# Seguidordelinea.net
KiCad netlist of a schematic drawn in Altium Designer
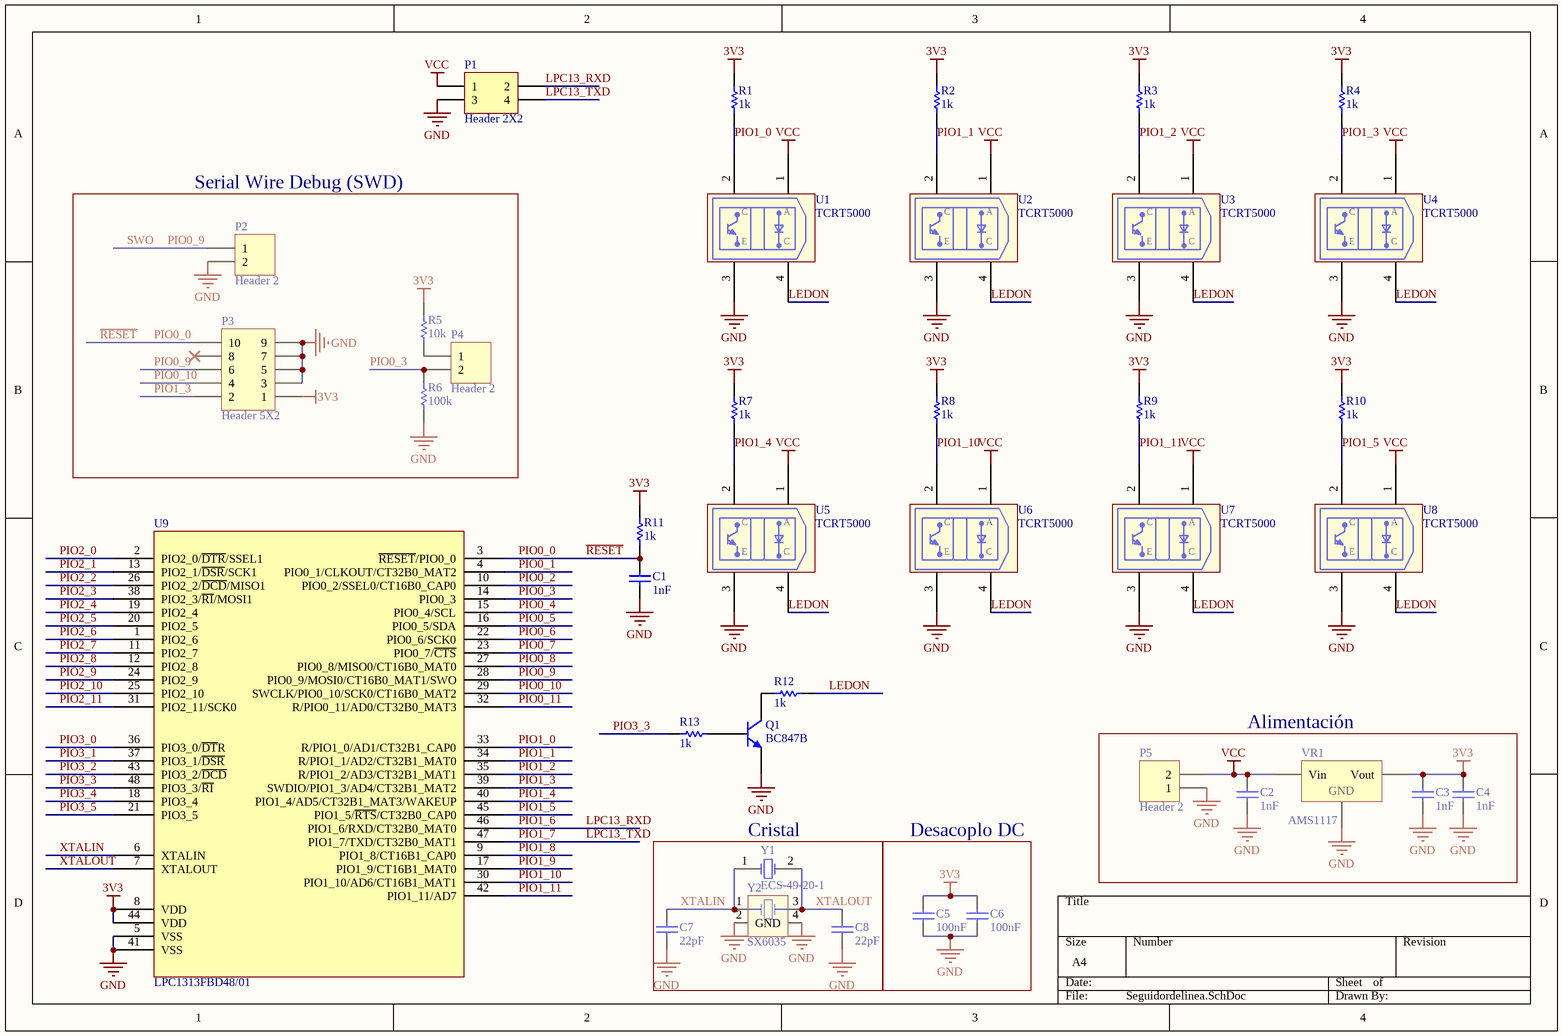
[diagram p0: Seguidordelinea.SchDoc]

(export (version "E")
  (design (tool "Eeschema 10.0.6"))
  (components
    (comp (ref "C1")
      (value "1nF")
      (footprint "0805_CAP")
      (fields (field (name "Comment") "Capacitor"))
      (libsource (lib "epf") (part "Cap"))
    )
    (comp (ref "C2")
      (value "1nF")
      (footprint "0805_CAP")
      (fields (field (name "Comment") "Capacitor"))
      (libsource (lib "epf") (part "Cap"))
    )
    (comp (ref "C3")
      (value "1nF")
      (footprint "0805_CAP")
      (fields (field (name "Comment") "Capacitor"))
      (libsource (lib "epf") (part "Cap"))
    )
    (comp (ref "C4")
      (value "1nF")
      (footprint "0805_CAP")
      (fields (field (name "Comment") "Capacitor"))
      (libsource (lib "epf") (part "Cap"))
    )
    (comp (ref "C5")
      (value "100nF")
      (footprint "0805_CAP")
      (fields (field (name "Comment") "Capacitor"))
      (libsource (lib "epf") (part "Cap"))
    )
    (comp (ref "C6")
      (value "100nF")
      (footprint "0805_CAP")
      (fields (field (name "Comment") "Capacitor"))
      (libsource (lib "epf") (part "Cap"))
    )
    (comp (ref "C7")
      (value "22pF")
      (footprint "0805_CAP")
      (fields (field (name "Comment") "Capacitor"))
      (libsource (lib "epf") (part "Cap"))
    )
    (comp (ref "C8")
      (value "22pF")
      (footprint "0805_CAP")
      (fields (field (name "Comment") "Capacitor"))
      (libsource (lib "epf") (part "Cap"))
    )
    (comp (ref "P1")
      (value "Header 2X2")
      (footprint "HDR2X2")
      (description "Header, 2-Pin, Dual row")
      (fields (field (name "PUBLISHER") "Altium Limited"))
      (libsource (lib "Miscellaneous Connectors") (part "Header 2X2"))
    )
    (comp (ref "P2")
      (value "Header 2")
      (footprint "HDR1X2")
      (description "Header, 2-Pin")
      (fields (field (name "PUBLISHER") "Altium Limited"))
      (libsource (lib "Miscellaneous Connectors") (part "Header 2"))
    )
    (comp (ref "P3")
      (value "Header 5X2")
      (footprint "HDR2X5")
      (description "Header, 5-Pin, Dual row")
      (fields (field (name "PUBLISHER") "Altium Limited"))
      (libsource (lib "epf") (part "Header 5X2"))
    )
    (comp (ref "P4")
      (value "Header 2")
      (footprint "HDR1X2")
      (description "Header, 2-Pin")
      (fields (field (name "PUBLISHER") "Altium Limited"))
      (libsource (lib "Miscellaneous Connectors") (part "Header 2"))
    )
    (comp (ref "P5")
      (value "Header 2")
      (footprint "HDR1X2")
      (description "Header, 2-Pin")
      (fields (field (name "PUBLISHER") "Altium Limited"))
      (libsource (lib "") (part "Header 2_1"))
    )
    (comp (ref "Q1")
      (value "BC847B")
      (footprint "SOT23")
      (description "NPN 100MHz")
      (libsource (lib "epf") (part "BC847B"))
    )
    (comp (ref "R1")
      (value "1k")
      (footprint "0805_RES")
      (fields (field (name "Comment") "Resistor"))
      (libsource (lib "epf") (part "Res"))
    )
    (comp (ref "R2")
      (value "1k")
      (footprint "0805_RES")
      (fields (field (name "Comment") "Resistor"))
      (libsource (lib "epf") (part "Res"))
    )
    (comp (ref "R3")
      (value "1k")
      (footprint "0805_RES")
      (fields (field (name "Comment") "Resistor"))
      (libsource (lib "epf") (part "Res"))
    )
    (comp (ref "R4")
      (value "1k")
      (footprint "0805_RES")
      (fields (field (name "Comment") "Resistor"))
      (libsource (lib "epf") (part "Res"))
    )
    (comp (ref "R5")
      (value "10k")
      (footprint "0805_RES")
      (fields (field (name "Comment") "Resistor"))
      (libsource (lib "epf") (part "Res"))
    )
    (comp (ref "R6")
      (value "100k")
      (footprint "0805_RES")
      (fields (field (name "Comment") "Resistor"))
      (libsource (lib "epf") (part "Res"))
    )
    (comp (ref "R7")
      (value "1k")
      (footprint "0805_RES")
      (fields (field (name "Comment") "Resistor"))
      (libsource (lib "epf") (part "Res"))
    )
    (comp (ref "R8")
      (value "1k")
      (footprint "0805_RES")
      (fields (field (name "Comment") "Resistor"))
      (libsource (lib "epf") (part "Res"))
    )
    (comp (ref "R9")
      (value "1k")
      (footprint "0805_RES")
      (fields (field (name "Comment") "Resistor"))
      (libsource (lib "epf") (part "Res"))
    )
    (comp (ref "R10")
      (value "1k")
      (footprint "0805_RES")
      (fields (field (name "Comment") "Resistor"))
      (libsource (lib "epf") (part "Res"))
    )
    (comp (ref "R11")
      (value "1k")
      (footprint "0805_RES")
      (fields (field (name "Comment") "Resistor"))
      (libsource (lib "epf") (part "Res"))
    )
    (comp (ref "R12")
      (value "1k")
      (footprint "0805_RES")
      (fields (field (name "Comment") "Resistor"))
      (libsource (lib "epf") (part "Res"))
    )
    (comp (ref "R13")
      (value "1k")
      (footprint "0805_RES")
      (fields (field (name "Comment") "Resistor"))
      (libsource (lib "epf") (part "Res"))
    )
    (comp (ref "U1") (value "TCRT5000") (footprint "TCRT5000") (libsource (lib "epf") (part "TCRT5000")))
    (comp (ref "U2") (value "TCRT5000") (footprint "TCRT5000") (libsource (lib "epf") (part "TCRT5000")))
    (comp (ref "U3") (value "TCRT5000") (footprint "TCRT5000") (libsource (lib "epf") (part "TCRT5000")))
    (comp (ref "U4") (value "TCRT5000") (footprint "TCRT5000") (libsource (lib "epf") (part "TCRT5000")))
    (comp (ref "U5") (value "TCRT5000") (footprint "TCRT5000") (libsource (lib "epf") (part "TCRT5000")))
    (comp (ref "U6") (value "TCRT5000") (footprint "TCRT5000") (libsource (lib "epf") (part "TCRT5000")))
    (comp (ref "U7") (value "TCRT5000") (footprint "TCRT5000") (libsource (lib "epf") (part "TCRT5000")))
    (comp (ref "U8") (value "TCRT5000") (footprint "TCRT5000") (libsource (lib "epf") (part "TCRT5000")))
    (comp (ref "U9")
      (value "LPC1313FBD48/01")
      (footprint "TQFP48_LPC1343")
      (description "ARM CortexM3 32K Flash, 8k RAM")
      (libsource (lib "epf") (part "LPC1313FBD48/01"))
    )
    (comp (ref "VR1")
      (value "AMS1117")
      (footprint "SOT-223 - M3")
      (description "Voltage Regulator")
      (fields (field (name "PUBLISHER") "Altium Limited"))
      (libsource (lib "epf") (part "AMS1117"))
    )
    (comp (ref "Y1")
      (value "ECS-49-20-1")
      (footprint "HC-49U")
      (description "Crystal Oscillator")
      (fields (field (name "PUBLISHER") "Altium Limited"))
      (libsource (lib "ECS Crystal Oscillator") (part "ECS-49-20-1"))
    )
    (comp (ref "Y2") (value "SX6035") (footprint "SX6035") (libsource (lib "epf") (part "XTAL_SX6035")))
  )
  (nets
    (net (code "1") (name "/LEDON") (class "Default")
      (node (ref "R12") (pin "2") (pinfunction "2_2") (pintype "passive"))
      (node (ref "U1") (pin "4") (pinfunction "C_4") (pintype "passive"))
      (node (ref "U2") (pin "4") (pinfunction "C_4") (pintype "passive"))
      (node (ref "U3") (pin "4") (pinfunction "C_4") (pintype "passive"))
      (node (ref "U4") (pin "4") (pinfunction "C_4") (pintype "passive"))
      (node (ref "U5") (pin "4") (pinfunction "C_4") (pintype "passive"))
      (node (ref "U6") (pin "4") (pinfunction "C_4") (pintype "passive"))
      (node (ref "U7") (pin "4") (pinfunction "C_4") (pintype "passive"))
      (node (ref "U8") (pin "4") (pinfunction "C_4") (pintype "passive"))
    )
    (net (code "2") (name "/LPC13_RXD") (class "Default")
      (node (ref "P1") (pin "2") (pinfunction "2_2") (pintype "passive"))
      (node (ref "U9") (pin "46") (pinfunction "PIO1_6/RXD/CT32B0_MAT0_46") (pintype "passive"))
    )
    (net (code "3") (name "/LPC13_TXD") (class "Default")
      (node (ref "P1") (pin "4") (pinfunction "4_4") (pintype "passive"))
      (node (ref "U9") (pin "47") (pinfunction "PIO1_7/TXD/CT32B0_MAT1_47") (pintype "passive"))
    )
    (net (code "4") (name "/PIO0_0") (class "Default")
      (node (ref "C1") (pin "2") (pinfunction "2_2") (pintype "passive"))
      (node (ref "P3") (pin "10") (pinfunction "10_10") (pintype "passive"))
      (node (ref "R11") (pin "1") (pinfunction "1_1") (pintype "passive"))
      (node (ref "U9") (pin "3") (pinfunction "~{RESET}/PIO0_0_3") (pintype "passive"))
    )
    (net (code "5") (name "/PIO0_1") (class "Default")
      (node (ref "U9") (pin "4") (pinfunction "PIO0_1/CLKOUT/CT32B0_MAT2_4") (pintype "passive"))
    )
    (net (code "6") (name "/PIO0_2") (class "Default")
      (node (ref "U9") (pin "10") (pinfunction "PIO0_2/SSEL0/CT16B0_CAP0_10") (pintype "passive"))
    )
    (net (code "7") (name "/PIO0_3") (class "Default")
      (node (ref "P4") (pin "2") (pinfunction "2_2") (pintype "passive"))
      (node (ref "R6") (pin "1") (pinfunction "1_1") (pintype "passive"))
      (node (ref "U9") (pin "14") (pinfunction "PIO0_3_14") (pintype "passive"))
    )
    (net (code "8") (name "/PIO0_4") (class "Default")
      (node (ref "U9") (pin "15") (pinfunction "PIO0_4/SCL_15") (pintype "passive"))
    )
    (net (code "9") (name "/PIO0_5") (class "Default")
      (node (ref "U9") (pin "16") (pinfunction "PIO0_5/SDA_16") (pintype "passive"))
    )
    (net (code "10") (name "/PIO0_6") (class "Default")
      (node (ref "U9") (pin "22") (pinfunction "PIO0_6/SCK0_22") (pintype "passive"))
    )
    (net (code "11") (name "/PIO0_7") (class "Default")
      (node (ref "U9") (pin "23") (pinfunction "PIO0_7/~{CTS}_23") (pintype "passive"))
    )
    (net (code "12") (name "/PIO0_8") (class "Default")
      (node (ref "U9") (pin "27") (pinfunction "PIO0_8/MISO0/CT16B0_MAT0_27") (pintype "passive"))
    )
    (net (code "13") (name "/PIO0_9") (class "Default")
      (node (ref "P2") (pin "1") (pinfunction "1_1") (pintype "passive"))
      (node (ref "P3") (pin "6") (pinfunction "6_6") (pintype "passive"))
      (node (ref "U9") (pin "28") (pinfunction "PIO0_9/MOSI0/CT16B0_MAT1/SWO_28") (pintype "passive"))
    )
    (net (code "14") (name "/PIO0_10") (class "Default")
      (node (ref "P3") (pin "4") (pinfunction "4_4") (pintype "passive"))
      (node (ref "U9") (pin "29") (pinfunction "SWCLK/PIO0_10/SCK0/CT16B0_MAT2_29") (pintype "passive"))
    )
    (net (code "15") (name "/PIO0_11") (class "Default")
      (node (ref "U9") (pin "32") (pinfunction "R/PIO0_11/AD0/CT32B0_MAT3_32") (pintype "passive"))
    )
    (net (code "16") (name "/PIO1_0") (class "Default")
      (node (ref "R1") (pin "2") (pinfunction "2_2") (pintype "passive"))
      (node (ref "U1") (pin "2") (pinfunction "C_2") (pintype "passive"))
      (node (ref "U9") (pin "33") (pinfunction "R/PIO1_0/AD1/CT32B1_CAP0_33") (pintype "passive"))
    )
    (net (code "17") (name "/PIO1_1") (class "Default")
      (node (ref "R2") (pin "2") (pinfunction "2_2") (pintype "passive"))
      (node (ref "U2") (pin "2") (pinfunction "C_2") (pintype "passive"))
      (node (ref "U9") (pin "34") (pinfunction "R/PIO1_1/AD2/CT32B1_MAT0_34") (pintype "passive"))
    )
    (net (code "18") (name "/PIO1_2") (class "Default")
      (node (ref "R3") (pin "2") (pinfunction "2_2") (pintype "passive"))
      (node (ref "U3") (pin "2") (pinfunction "C_2") (pintype "passive"))
      (node (ref "U9") (pin "35") (pinfunction "R/PIO1_2/AD3/CT32B1_MAT1_35") (pintype "passive"))
    )
    (net (code "19") (name "/PIO1_3") (class "Default")
      (node (ref "P3") (pin "2") (pinfunction "2_2") (pintype "passive"))
      (node (ref "R4") (pin "2") (pinfunction "2_2") (pintype "passive"))
      (node (ref "U4") (pin "2") (pinfunction "C_2") (pintype "passive"))
      (node (ref "U9") (pin "39") (pinfunction "SWDIO/PIO1_3/AD4/CT32B1_MAT2_39") (pintype "passive"))
    )
    (net (code "20") (name "/PIO1_4") (class "Default")
      (node (ref "R7") (pin "2") (pinfunction "2_2") (pintype "passive"))
      (node (ref "U5") (pin "2") (pinfunction "C_2") (pintype "passive"))
      (node (ref "U9") (pin "40") (pinfunction "PIO1_4/AD5/CT32B1_MAT3/WAKEUP_40") (pintype "passive"))
    )
    (net (code "21") (name "/PIO1_5") (class "Default")
      (node (ref "R10") (pin "2") (pinfunction "2_2") (pintype "passive"))
      (node (ref "U8") (pin "2") (pinfunction "C_2") (pintype "passive"))
      (node (ref "U9") (pin "45") (pinfunction "PIO1_5/~{RTS}/CT32B0_CAP0_45") (pintype "passive"))
    )
    (net (code "22") (name "/PIO1_8") (class "Default")
      (node (ref "U9") (pin "9") (pinfunction "PIO1_8/CT16B1_CAP0_9") (pintype "passive"))
    )
    (net (code "23") (name "/PIO1_9") (class "Default")
      (node (ref "U9") (pin "17") (pinfunction "PIO1_9/CT16B1_MAT0_17") (pintype "passive"))
    )
    (net (code "24") (name "/PIO1_10") (class "Default")
      (node (ref "R8") (pin "2") (pinfunction "2_2") (pintype "passive"))
      (node (ref "U6") (pin "2") (pinfunction "C_2") (pintype "passive"))
      (node (ref "U9") (pin "30") (pinfunction "PIO1_10/AD6/CT16B1_MAT1_30") (pintype "passive"))
    )
    (net (code "25") (name "/PIO1_11") (class "Default")
      (node (ref "R9") (pin "2") (pinfunction "2_2") (pintype "passive"))
      (node (ref "U7") (pin "2") (pinfunction "C_2") (pintype "passive"))
      (node (ref "U9") (pin "42") (pinfunction "PIO1_11/AD7_42") (pintype "passive"))
    )
    (net (code "26") (name "/PIO2_0") (class "Default")
      (node (ref "U9") (pin "2") (pinfunction "PIO2_0/~{DTR}/SSEL1_2") (pintype "passive"))
    )
    (net (code "27") (name "/PIO2_1") (class "Default")
      (node (ref "U9") (pin "13") (pinfunction "PIO2_1/~{DSR}/SCK1_13") (pintype "passive"))
    )
    (net (code "28") (name "/PIO2_2") (class "Default")
      (node (ref "U9") (pin "26") (pinfunction "PIO2_2/~{DCD}/MISO1_26") (pintype "passive"))
    )
    (net (code "29") (name "/PIO2_3") (class "Default")
      (node (ref "U9") (pin "38") (pinfunction "PIO2_3/~{RI}/MOSI1_38") (pintype "passive"))
    )
    (net (code "30") (name "/PIO2_4") (class "Default")
      (node (ref "U9") (pin "19") (pinfunction "PIO2_4_19") (pintype "passive"))
    )
    (net (code "31") (name "/PIO2_5") (class "Default")
      (node (ref "U9") (pin "20") (pinfunction "PIO2_5_20") (pintype "passive"))
    )
    (net (code "32") (name "/PIO2_6") (class "Default")
      (node (ref "U9") (pin "1") (pinfunction "PIO2_6_1") (pintype "passive"))
    )
    (net (code "33") (name "/PIO2_7") (class "Default")
      (node (ref "U9") (pin "11") (pinfunction "PIO2_7_11") (pintype "passive"))
    )
    (net (code "34") (name "/PIO2_8") (class "Default")
      (node (ref "U9") (pin "12") (pinfunction "PIO2_8_12") (pintype "passive"))
    )
    (net (code "35") (name "/PIO2_9") (class "Default")
      (node (ref "U9") (pin "24") (pinfunction "PIO2_9_24") (pintype "passive"))
    )
    (net (code "36") (name "/PIO2_10") (class "Default")
      (node (ref "U9") (pin "25") (pinfunction "PIO2_10_25") (pintype "passive"))
    )
    (net (code "37") (name "/PIO2_11") (class "Default")
      (node (ref "U9") (pin "31") (pinfunction "PIO2_11/SCK0_31") (pintype "passive"))
    )
    (net (code "38") (name "/PIO3_0") (class "Default")
      (node (ref "U9") (pin "36") (pinfunction "PIO3_0/~{DT}R_36") (pintype "passive"))
    )
    (net (code "39") (name "/PIO3_1") (class "Default")
      (node (ref "U9") (pin "37") (pinfunction "PIO3_1/~{DSR}_37") (pintype "passive"))
    )
    (net (code "40") (name "/PIO3_2") (class "Default")
      (node (ref "U9") (pin "43") (pinfunction "PIO3_2/~{DCD}_43") (pintype "passive"))
    )
    (net (code "41") (name "/PIO3_3") (class "Default")
      (node (ref "R13") (pin "1") (pinfunction "1_1") (pintype "passive"))
      (node (ref "U9") (pin "48") (pinfunction "PIO3_3/~{RI}_48") (pintype "passive"))
    )
    (net (code "42") (name "/PIO3_4") (class "Default")
      (node (ref "U9") (pin "18") (pinfunction "PIO3_4_18") (pintype "passive"))
    )
    (net (code "43") (name "/PIO3_5") (class "Default")
      (node (ref "U9") (pin "21") (pinfunction "PIO3_5_21") (pintype "passive"))
    )
    (net (code "44") (name "/XTALIN") (class "Default")
      (node (ref "C7") (pin "2") (pinfunction "2_2") (pintype "passive"))
      (node (ref "U9") (pin "6") (pinfunction "XTALIN_6") (pintype "passive"))
      (node (ref "Y1") (pin "1") (pinfunction "OSC1_1") (pintype "passive"))
      (node (ref "Y2") (pin "1") (pinfunction "XTAL_1") (pintype "passive"))
    )
    (net (code "45") (name "/XTALOUT") (class "Default")
      (node (ref "C8") (pin "1") (pinfunction "1_1") (pintype "passive"))
      (node (ref "U9") (pin "7") (pinfunction "XTALOUT_7") (pintype "passive"))
      (node (ref "Y1") (pin "2") (pinfunction "OSC2_2") (pintype "passive"))
      (node (ref "Y2") (pin "3") (pinfunction "XTAL_3") (pintype "passive"))
    )
    (net (code "46") (name "3V3") (class "Default")
      (node (ref "C3") (pin "2") (pinfunction "2_2") (pintype "passive"))
      (node (ref "C4") (pin "2") (pinfunction "2_2") (pintype "passive"))
      (node (ref "C5") (pin "2") (pinfunction "2_2") (pintype "passive"))
      (node (ref "C6") (pin "2") (pinfunction "2_2") (pintype "passive"))
      (node (ref "P3") (pin "1") (pinfunction "1_1") (pintype "passive"))
      (node (ref "R1") (pin "1") (pinfunction "1_1") (pintype "passive"))
      (node (ref "R10") (pin "1") (pinfunction "1_1") (pintype "passive"))
      (node (ref "R11") (pin "2") (pinfunction "2_2") (pintype "passive"))
      (node (ref "R2") (pin "1") (pinfunction "1_1") (pintype "passive"))
      (node (ref "R3") (pin "1") (pinfunction "1_1") (pintype "passive"))
      (node (ref "R4") (pin "1") (pinfunction "1_1") (pintype "passive"))
      (node (ref "R5") (pin "1") (pinfunction "1_1") (pintype "passive"))
      (node (ref "R7") (pin "1") (pinfunction "1_1") (pintype "passive"))
      (node (ref "R8") (pin "1") (pinfunction "1_1") (pintype "passive"))
      (node (ref "R9") (pin "1") (pinfunction "1_1") (pintype "passive"))
      (node (ref "U9") (pin "44") (pinfunction "VDD_44") (pintype "passive"))
      (node (ref "U9") (pin "8") (pinfunction "VDD_8") (pintype "passive"))
      (node (ref "VR1") (pin "2") (pinfunction "Vout_2") (pintype "passive"))
    )
    (net (code "47") (name "GND") (class "Default")
      (node (ref "C1") (pin "1") (pinfunction "1_1") (pintype "passive"))
      (node (ref "C2") (pin "1") (pinfunction "1_1") (pintype "passive"))
      (node (ref "C3") (pin "1") (pinfunction "1_1") (pintype "passive"))
      (node (ref "C4") (pin "1") (pinfunction "1_1") (pintype "passive"))
      (node (ref "C5") (pin "1") (pinfunction "1_1") (pintype "passive"))
      (node (ref "C6") (pin "1") (pinfunction "1_1") (pintype "passive"))
      (node (ref "C7") (pin "1") (pinfunction "1_1") (pintype "passive"))
      (node (ref "C8") (pin "2") (pinfunction "2_2") (pintype "passive"))
      (node (ref "P1") (pin "3") (pinfunction "3_3") (pintype "passive"))
      (node (ref "P2") (pin "2") (pinfunction "2_2") (pintype "passive"))
      (node (ref "P3") (pin "3") (pinfunction "3_3") (pintype "passive"))
      (node (ref "P3") (pin "5") (pinfunction "5_5") (pintype "passive"))
      (node (ref "P3") (pin "7") (pinfunction "7_7") (pintype "passive"))
      (node (ref "P3") (pin "9") (pinfunction "9_9") (pintype "passive"))
      (node (ref "P5") (pin "1") (pinfunction "1_1") (pintype "passive"))
      (node (ref "Q1") (pin "2") (pinfunction "E_2") (pintype "passive"))
      (node (ref "R6") (pin "2") (pinfunction "2_2") (pintype "passive"))
      (node (ref "U1") (pin "3") (pinfunction "E_3") (pintype "passive"))
      (node (ref "U2") (pin "3") (pinfunction "E_3") (pintype "passive"))
      (node (ref "U3") (pin "3") (pinfunction "E_3") (pintype "passive"))
      (node (ref "U4") (pin "3") (pinfunction "E_3") (pintype "passive"))
      (node (ref "U5") (pin "3") (pinfunction "E_3") (pintype "passive"))
      (node (ref "U6") (pin "3") (pinfunction "E_3") (pintype "passive"))
      (node (ref "U7") (pin "3") (pinfunction "E_3") (pintype "passive"))
      (node (ref "U8") (pin "3") (pinfunction "E_3") (pintype "passive"))
      (node (ref "U9") (pin "41") (pinfunction "VSS_41") (pintype "passive"))
      (node (ref "U9") (pin "5") (pinfunction "VSS_5") (pintype "passive"))
      (node (ref "VR1") (pin "1") (pinfunction "GND_1") (pintype "passive"))
      (node (ref "Y2") (pin "2") (pinfunction "GND_2") (pintype "passive"))
      (node (ref "Y2") (pin "4") (pinfunction "GND_4") (pintype "passive"))
    )
    (net (code "48") (name "Net-(P4-Pad1)") (class "Default")
      (node (ref "P4") (pin "1") (pinfunction "1_1") (pintype "passive"))
      (node (ref "R5") (pin "2") (pinfunction "2_2") (pintype "passive"))
    )
    (net (code "49") (name "Net-(Q1-B)") (class "Default")
      (node (ref "Q1") (pin "1") (pinfunction "B_1") (pintype "passive"))
      (node (ref "R13") (pin "2") (pinfunction "2_2") (pintype "passive"))
    )
    (net (code "50") (name "Net-(Q1-C)") (class "Default")
      (node (ref "Q1") (pin "3") (pinfunction "C_3") (pintype "passive"))
      (node (ref "R12") (pin "1") (pinfunction "1_1") (pintype "passive"))
    )
    (net (code "51") (name "VCC") (class "Default")
      (node (ref "C2") (pin "2") (pinfunction "2_2") (pintype "passive"))
      (node (ref "P1") (pin "1") (pinfunction "1_1") (pintype "passive"))
      (node (ref "P5") (pin "2") (pinfunction "2_2") (pintype "passive"))
      (node (ref "U1") (pin "1") (pinfunction "A_1") (pintype "passive"))
      (node (ref "U2") (pin "1") (pinfunction "A_1") (pintype "passive"))
      (node (ref "U3") (pin "1") (pinfunction "A_1") (pintype "passive"))
      (node (ref "U4") (pin "1") (pinfunction "A_1") (pintype "passive"))
      (node (ref "U5") (pin "1") (pinfunction "A_1") (pintype "passive"))
      (node (ref "U6") (pin "1") (pinfunction "A_1") (pintype "passive"))
      (node (ref "U7") (pin "1") (pinfunction "A_1") (pintype "passive"))
      (node (ref "U8") (pin "1") (pinfunction "A_1") (pintype "passive"))
      (node (ref "VR1") (pin "3") (pinfunction "Vin_3") (pintype "passive"))
    )
    (net (code "52") (name "unconnected-(P3-Pad8)") (class "Default")
      (node (ref "P3") (pin "8") (pinfunction "8_8") (pintype "passive+no_connect"))
    )
  )
)
